# BQ27545.net
KiCad netlist of a schematic drawn in EAGLE
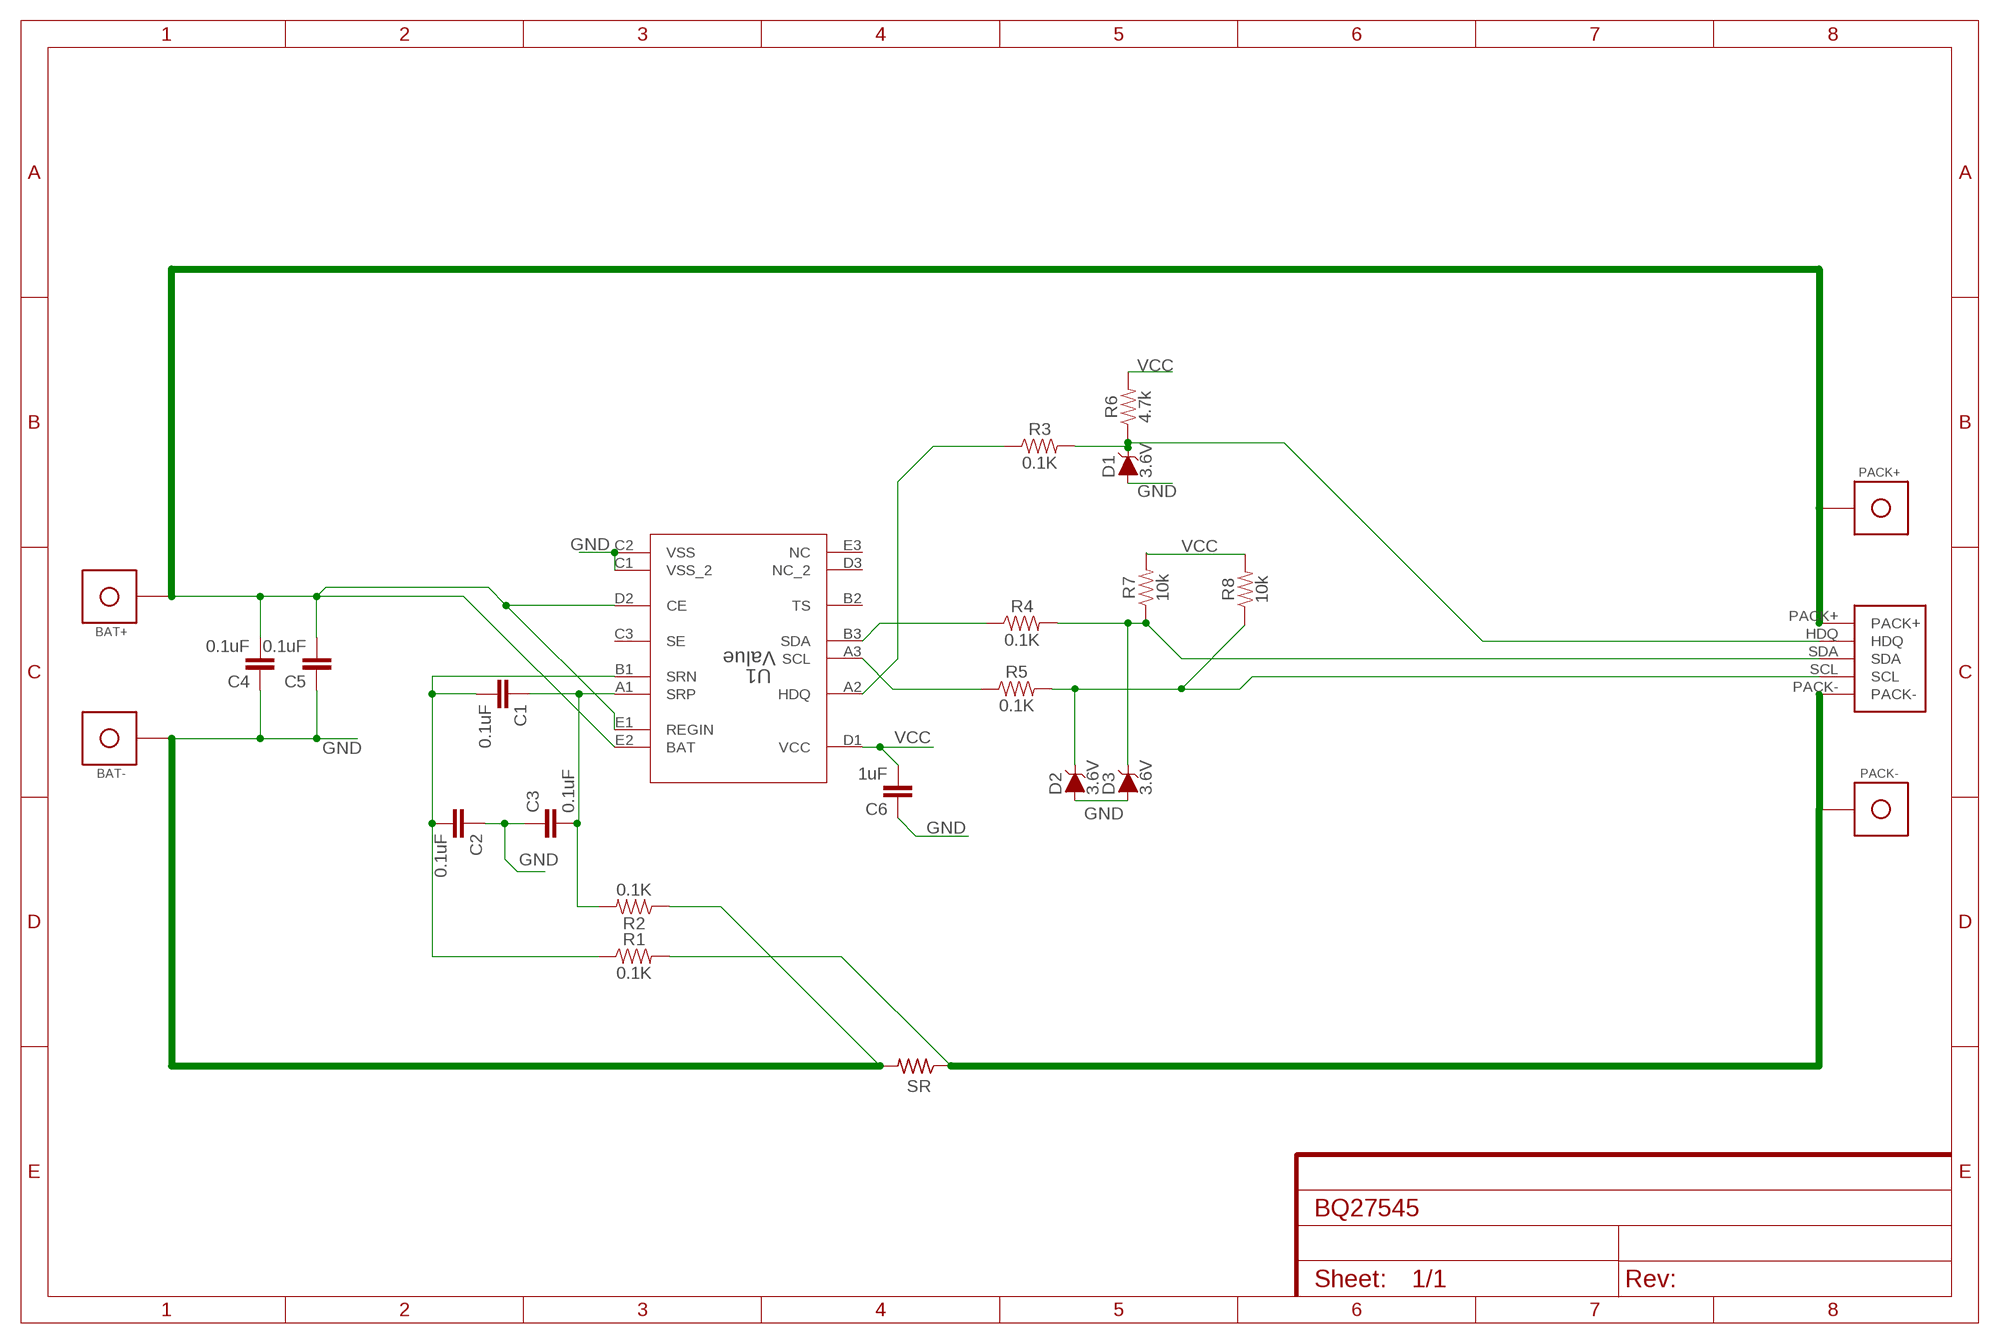
[diagram p0: schematic, sheet 1]

(export (version "E")
  (design (tool "Eeschema 10.0.6"))
  (components
    (comp (ref "BAT+")
      (value "BAT_TAB")
      (footprint "eagle-import:BATT_TAB")
      (libsource (lib "eagle-import") (part "BAT_TAB"))
    )
    (comp (ref "BAT-")
      (value "BAT_TAB")
      (footprint "eagle-import:BATT_TAB")
      (libsource (lib "eagle-import") (part "BAT_TAB"))
    )
    (comp (ref "C1")
      (value "0.1uF")
      (footprint "eagle-import:0402")
      (libsource (lib "eagle-import") (part "0.1UF-0402-16V-10%"))
    )
    (comp (ref "C2")
      (value "0.1uF")
      (footprint "eagle-import:0402")
      (libsource (lib "eagle-import") (part "0.1UF-0402-16V-10%"))
    )
    (comp (ref "C3")
      (value "0.1uF")
      (footprint "eagle-import:0402")
      (libsource (lib "eagle-import") (part "0.1UF-0402-16V-10%"))
    )
    (comp (ref "C4")
      (value "0.1uF")
      (footprint "eagle-import:0402")
      (libsource (lib "eagle-import") (part "0.1UF-0402-16V-10%"))
    )
    (comp (ref "C5")
      (value "0.1uF")
      (footprint "eagle-import:0402")
      (libsource (lib "eagle-import") (part "0.1UF-0402-16V-10%"))
    )
    (comp (ref "C6")
      (value "1uF")
      (footprint "eagle-import:0402")
      (libsource (lib "eagle-import") (part "0.1UF-0402-16V-10%"))
    )
    (comp (ref "D1")
      (value "3.6V")
      (footprint "eagle-import:SOD-323")
      (libsource (lib "eagle-import") (part "DIODE-ZENER-BZT52C3V6S"))
    )
    (comp (ref "D2")
      (value "3.6V")
      (footprint "eagle-import:SOD-323")
      (libsource (lib "eagle-import") (part "DIODE-ZENER-BZT52C3V6S"))
    )
    (comp (ref "D3")
      (value "3.6V")
      (footprint "eagle-import:SOD-323")
      (libsource (lib "eagle-import") (part "DIODE-ZENER-BZT52C3V6S"))
    )
    (comp (ref "PACK+")
      (value "BAT_TAB")
      (footprint "eagle-import:BATT_TAB")
      (libsource (lib "eagle-import") (part "BAT_TAB"))
    )
    (comp (ref "PACK-")
      (value "BAT_TAB")
      (footprint "eagle-import:BATT_TAB")
      (libsource (lib "eagle-import") (part "BAT_TAB"))
    )
    (comp (ref "R1")
      (value "0.1K")
      (footprint "eagle-import:0402")
      (libsource (lib "eagle-import") (part "RESISTOR0402"))
    )
    (comp (ref "R2")
      (value "0.1K")
      (footprint "eagle-import:0402")
      (libsource (lib "eagle-import") (part "RESISTOR0402"))
    )
    (comp (ref "R3")
      (value "0.1K")
      (footprint "eagle-import:0402")
      (libsource (lib "eagle-import") (part "RESISTOR0402"))
    )
    (comp (ref "R4")
      (value "0.1K")
      (footprint "eagle-import:0402")
      (libsource (lib "eagle-import") (part "RESISTOR0402"))
    )
    (comp (ref "R5")
      (value "0.1K")
      (footprint "eagle-import:0402")
      (libsource (lib "eagle-import") (part "RESISTOR0402"))
    )
    (comp (ref "R6")
      (value "4.7k")
      (footprint "eagle-import:0402")
      (libsource (lib "eagle-import") (part "RESISTOR0402"))
    )
    (comp (ref "R7")
      (value "10k")
      (footprint "eagle-import:0402")
      (libsource (lib "eagle-import") (part "RESISTOR0402"))
    )
    (comp (ref "R8")
      (value "10k")
      (footprint "eagle-import:0402")
      (libsource (lib "eagle-import") (part "RESISTOR0402"))
    )
    (comp (ref "SR")
      (value "R-US_R2512")
      (footprint "eagle-import:R2512")
      (libsource (lib "eagle-import") (part "R-US_R2512"))
    )
    (comp (ref "U$1")
      (value "BAT_COMM_PWR_REV")
      (footprint "eagle-import:BATT_COMM_PWR_REV")
      (libsource (lib "eagle-import") (part "BAT_COMM_PWR_REV"))
    )
    (comp (ref "U1")
      (value "Value")
      (footprint "eagle-import:YZF0015BBBP")
      (fields
        (field (name "ALTERNATEPARTNUMBER") "BQ27546YZFTG1")
        (field (name "MANUFACTURER") "Texas Instruments")
        (field (name "PARTNUMBER") "BQ27546YZFRG1")
      )
      (libsource (lib "eagle-import") (part "BQ27545_YZFR-G1"))
    )
  )
  (nets
    (net (code "1") (name "/GND") (class "Default")
      (node (ref "BAT-") (pin "P$1") (pinfunction "P$1_P$1") (pintype "power_in"))
      (node (ref "C2") (pin "1") (pinfunction "1_1") (pintype "passive"))
      (node (ref "C3") (pin "1") (pinfunction "1_1") (pintype "passive"))
      (node (ref "C4") (pin "1") (pinfunction "1_1") (pintype "passive"))
      (node (ref "C5") (pin "1") (pinfunction "1_1") (pintype "passive"))
      (node (ref "C6") (pin "1") (pinfunction "1_1") (pintype "passive"))
      (node (ref "D1") (pin "A") (pinfunction "A_A") (pintype "passive"))
      (node (ref "D2") (pin "A") (pinfunction "A_A") (pintype "passive"))
      (node (ref "D3") (pin "A") (pinfunction "A_A") (pintype "passive"))
      (node (ref "R2") (pin "1") (pinfunction "1_1") (pintype "passive"))
      (node (ref "SR") (pin "2") (pinfunction "2_2") (pintype "passive"))
      (node (ref "U1") (pin "C1") (pinfunction "VSS_2_C1") (pintype "power_in"))
      (node (ref "U1") (pin "C2") (pinfunction "VSS_C2") (pintype "power_in"))
    )
    (net (code "2") (name "/VCC") (class "Default")
      (node (ref "C6") (pin "2") (pinfunction "2_2") (pintype "passive"))
      (node (ref "R6") (pin "2") (pinfunction "2_2") (pintype "passive"))
      (node (ref "R7") (pin "2") (pinfunction "2_2") (pintype "passive"))
      (node (ref "R8") (pin "2") (pinfunction "2_2") (pintype "passive"))
      (node (ref "U1") (pin "D1") (pinfunction "VCC_D1") (pintype "power_in"))
    )
    (net (code "3") (name "Net-(D1-PadC)") (class "Default")
      (node (ref "D1") (pin "C") (pinfunction "C_C") (pintype "passive"))
      (node (ref "R3") (pin "2") (pinfunction "2_2") (pintype "passive"))
      (node (ref "R6") (pin "1") (pinfunction "1_1") (pintype "passive"))
      (node (ref "U$1") (pin "HDQ") (pinfunction "HDQ_HDQ") (pintype "bidirectional"))
    )
    (net (code "4") (name "Net-(D2-PadC)") (class "Default")
      (node (ref "D2") (pin "C") (pinfunction "C_C") (pintype "passive"))
      (node (ref "R5") (pin "2") (pinfunction "2_2") (pintype "passive"))
      (node (ref "R8") (pin "1") (pinfunction "1_1") (pintype "passive"))
      (node (ref "U$1") (pin "SCL") (pinfunction "SCL_SCL") (pintype "bidirectional"))
    )
    (net (code "5") (name "Net-(D3-PadC)") (class "Default")
      (node (ref "D3") (pin "C") (pinfunction "C_C") (pintype "passive"))
      (node (ref "R4") (pin "2") (pinfunction "2_2") (pintype "passive"))
      (node (ref "R7") (pin "1") (pinfunction "1_1") (pintype "passive"))
      (node (ref "U$1") (pin "SDA") (pinfunction "SDA_SDA") (pintype "bidirectional"))
    )
    (net (code "6") (name "Net-(PACK--PadP$1)") (class "Default")
      (node (ref "PACK-") (pin "P$1") (pinfunction "P$1_P$1") (pintype "power_in"))
      (node (ref "R1") (pin "2") (pinfunction "2_2") (pintype "passive"))
      (node (ref "SR") (pin "1") (pinfunction "1_1") (pintype "passive"))
      (node (ref "U$1") (pin "PACK-") (pinfunction "PACK-_PACK-") (pintype "power_in"))
    )
    (net (code "7") (name "Net-(U1-BAT)") (class "Default")
      (node (ref "BAT+") (pin "P$1") (pinfunction "P$1_P$1") (pintype "power_in"))
      (node (ref "C4") (pin "2") (pinfunction "2_2") (pintype "passive"))
      (node (ref "C5") (pin "2") (pinfunction "2_2") (pintype "passive"))
      (node (ref "PACK+") (pin "P$1") (pinfunction "P$1_P$1") (pintype "power_in"))
      (node (ref "U$1") (pin "PACK+") (pinfunction "PACK+_PACK+") (pintype "power_in"))
      (node (ref "U1") (pin "D2") (pinfunction "CE_D2") (pintype "input"))
      (node (ref "U1") (pin "E1") (pinfunction "REGIN_E1") (pintype "power_in"))
      (node (ref "U1") (pin "E2") (pinfunction "BAT_E2") (pintype "input"))
    )
    (net (code "8") (name "Net-(U1-HDQ)") (class "Default")
      (node (ref "R3") (pin "1") (pinfunction "1_1") (pintype "passive"))
      (node (ref "U1") (pin "A2") (pinfunction "HDQ_A2") (pintype "bidirectional"))
    )
    (net (code "9") (name "Net-(U1-SCL)") (class "Default")
      (node (ref "R5") (pin "1") (pinfunction "1_1") (pintype "passive"))
      (node (ref "U1") (pin "A3") (pinfunction "SCL_A3") (pintype "input"))
    )
    (net (code "10") (name "Net-(U1-SDA)") (class "Default")
      (node (ref "R4") (pin "1") (pinfunction "1_1") (pintype "passive"))
      (node (ref "U1") (pin "B3") (pinfunction "SDA_B3") (pintype "bidirectional"))
    )
    (net (code "11") (name "Net-(U1-SRN)") (class "Default")
      (node (ref "C1") (pin "2") (pinfunction "2_2") (pintype "passive"))
      (node (ref "C2") (pin "2") (pinfunction "2_2") (pintype "passive"))
      (node (ref "R1") (pin "1") (pinfunction "1_1") (pintype "passive"))
      (node (ref "U1") (pin "B1") (pinfunction "SRN_B1") (pintype "input"))
    )
    (net (code "12") (name "Net-(U1-SRP)") (class "Default")
      (node (ref "C1") (pin "1") (pinfunction "1_1") (pintype "passive"))
      (node (ref "C3") (pin "2") (pinfunction "2_2") (pintype "passive"))
      (node (ref "R2") (pin "2") (pinfunction "2_2") (pintype "passive"))
      (node (ref "U1") (pin "A1") (pinfunction "SRP_A1") (pintype "input"))
    )
    (net (code "13") (name "unconnected-(U1-NC-PadE3)") (class "Default")
      (node (ref "U1") (pin "E3") (pinfunction "NC_E3") (pintype "passive"))
    )
    (net (code "14") (name "unconnected-(U1-NC_2-PadD3)") (class "Default")
      (node (ref "U1") (pin "D3") (pinfunction "NC_2_D3") (pintype "passive"))
    )
    (net (code "15") (name "unconnected-(U1-SE-PadC3)") (class "Default")
      (node (ref "U1") (pin "C3") (pinfunction "SE_C3") (pintype "tri_state"))
    )
    (net (code "16") (name "unconnected-(U1-TS-PadB2)") (class "Default")
      (node (ref "U1") (pin "B2") (pinfunction "TS_B2") (pintype "input"))
    )
  )
)
